# supply.net
KiCad netlist of a schematic drawn in EAGLE
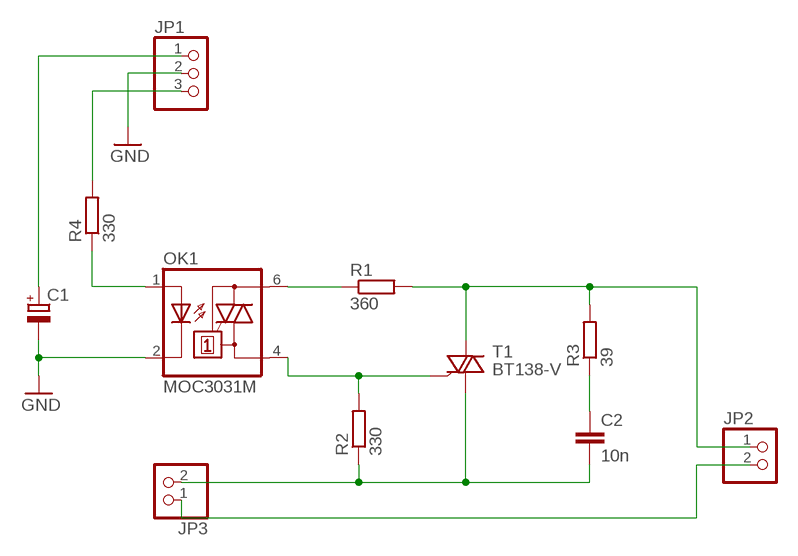
[diagram p0: schematic, sheet 1]

(export (version "E")
  (design (tool "Eeschema 10.0.6"))
  (components
    (comp (ref "C1")
      (value "CPOL-EUE5-10.5")
      (footprint "eagle-import:E5-10,5")
      (libsource (lib "eagle-import") (part "CPOL-EUE5-10.5"))
    )
    (comp (ref "C2")
      (value "10n")
      (footprint "eagle-import:C102-064X133")
      (libsource (lib "eagle-import") (part "C-EU102-064X133"))
    )
    (comp (ref "JP1")
      (value "PINHD-1X3")
      (footprint "eagle-import:1X03")
      (libsource (lib "eagle-import") (part "PINHD-1X3"))
    )
    (comp (ref "JP2")
      (value "PINHD-1X2")
      (footprint "eagle-import:1X02")
      (libsource (lib "eagle-import") (part "PINHD-1X2"))
    )
    (comp (ref "JP3")
      (value "PINHD-1X2")
      (footprint "eagle-import:1X02")
      (libsource (lib "eagle-import") (part "PINHD-1X2"))
    )
    (comp (ref "OK1")
      (value "MOC3031M")
      (footprint "eagle-import:DIL06")
      (fields (field (name "MF") "FAIRCHILD SEMICONDUCTOR"))
      (libsource (lib "eagle-import") (part "MOC3031M"))
    )
    (comp (ref "R1")
      (value "360")
      (footprint "eagle-import:0207_10")
      (libsource (lib "eagle-import") (part "R-EU_0207/10"))
    )
    (comp (ref "R2")
      (value "330")
      (footprint "eagle-import:0207_10")
      (libsource (lib "eagle-import") (part "R-EU_0207/10"))
    )
    (comp (ref "R3")
      (value "39")
      (footprint "eagle-import:0207_10")
      (libsource (lib "eagle-import") (part "R-EU_0207/10"))
    )
    (comp (ref "R4")
      (value "330")
      (footprint "eagle-import:0207_10")
      (libsource (lib "eagle-import") (part "R-EU_0207/10"))
    )
    (comp (ref "T1")
      (value "BT138-V")
      (footprint "eagle-import:TO220BV")
      (libsource (lib "eagle-import") (part "BT138-V"))
    )
  )
  (nets
    (net (code "1") (name "GND") (class "Default")
      (node (ref "C1") (pin "-") (pinfunction "-_-") (pintype "passive"))
      (node (ref "JP1") (pin "2") (pinfunction "2_2") (pintype "passive"))
      (node (ref "OK1") (pin "2") (pinfunction "C_2") (pintype "passive"))
    )
    (net (code "2") (name "Net-(C1-Pad+)") (class "Default")
      (node (ref "C1") (pin "+") (pinfunction "+_+") (pintype "passive"))
      (node (ref "JP1") (pin "1") (pinfunction "1_1") (pintype "passive"))
    )
    (net (code "3") (name "Net-(C2-Pad1)") (class "Default")
      (node (ref "C2") (pin "1") (pinfunction "1_1") (pintype "passive"))
      (node (ref "R3") (pin "1") (pinfunction "1_1") (pintype "passive"))
    )
    (net (code "4") (name "Net-(JP1-Pad3)") (class "Default")
      (node (ref "JP1") (pin "3") (pinfunction "3_3") (pintype "passive"))
      (node (ref "R4") (pin "2") (pinfunction "2_2") (pintype "passive"))
    )
    (net (code "5") (name "Net-(JP2-Pad2)") (class "Default")
      (node (ref "JP2") (pin "2") (pinfunction "2_2") (pintype "passive"))
      (node (ref "JP3") (pin "1") (pinfunction "1_1") (pintype "passive"))
    )
    (net (code "6") (name "Net-(OK1-A)") (class "Default")
      (node (ref "OK1") (pin "1") (pinfunction "A_1") (pintype "passive"))
      (node (ref "R4") (pin "1") (pinfunction "1_1") (pintype "passive"))
    )
    (net (code "7") (name "Net-(OK1-A1)") (class "Default")
      (node (ref "OK1") (pin "4") (pinfunction "A1_4") (pintype "passive"))
      (node (ref "R2") (pin "2") (pinfunction "2_2") (pintype "passive"))
      (node (ref "T1") (pin "G") (pinfunction "G_G") (pintype "passive"))
    )
    (net (code "8") (name "Net-(OK1-A2)") (class "Default")
      (node (ref "OK1") (pin "6") (pinfunction "A2_6") (pintype "passive"))
      (node (ref "R1") (pin "1") (pinfunction "1_1") (pintype "passive"))
    )
    (net (code "9") (name "Net-(T1-A1)") (class "Default")
      (node (ref "C2") (pin "2") (pinfunction "2_2") (pintype "passive"))
      (node (ref "JP3") (pin "2") (pinfunction "2_2") (pintype "passive"))
      (node (ref "R2") (pin "1") (pinfunction "1_1") (pintype "passive"))
      (node (ref "T1") (pin "T1") (pinfunction "A1_T1") (pintype "passive"))
    )
    (net (code "10") (name "Net-(T1-A2)") (class "Default")
      (node (ref "JP2") (pin "1") (pinfunction "1_1") (pintype "passive"))
      (node (ref "R1") (pin "2") (pinfunction "2_2") (pintype "passive"))
      (node (ref "R3") (pin "2") (pinfunction "2_2") (pintype "passive"))
      (node (ref "T1") (pin "T2") (pinfunction "A2_T2") (pintype "passive"))
    )
  )
)
